# Qwiic_UV_Sensor_VEML6075.net
KiCad netlist of a schematic drawn in EAGLE
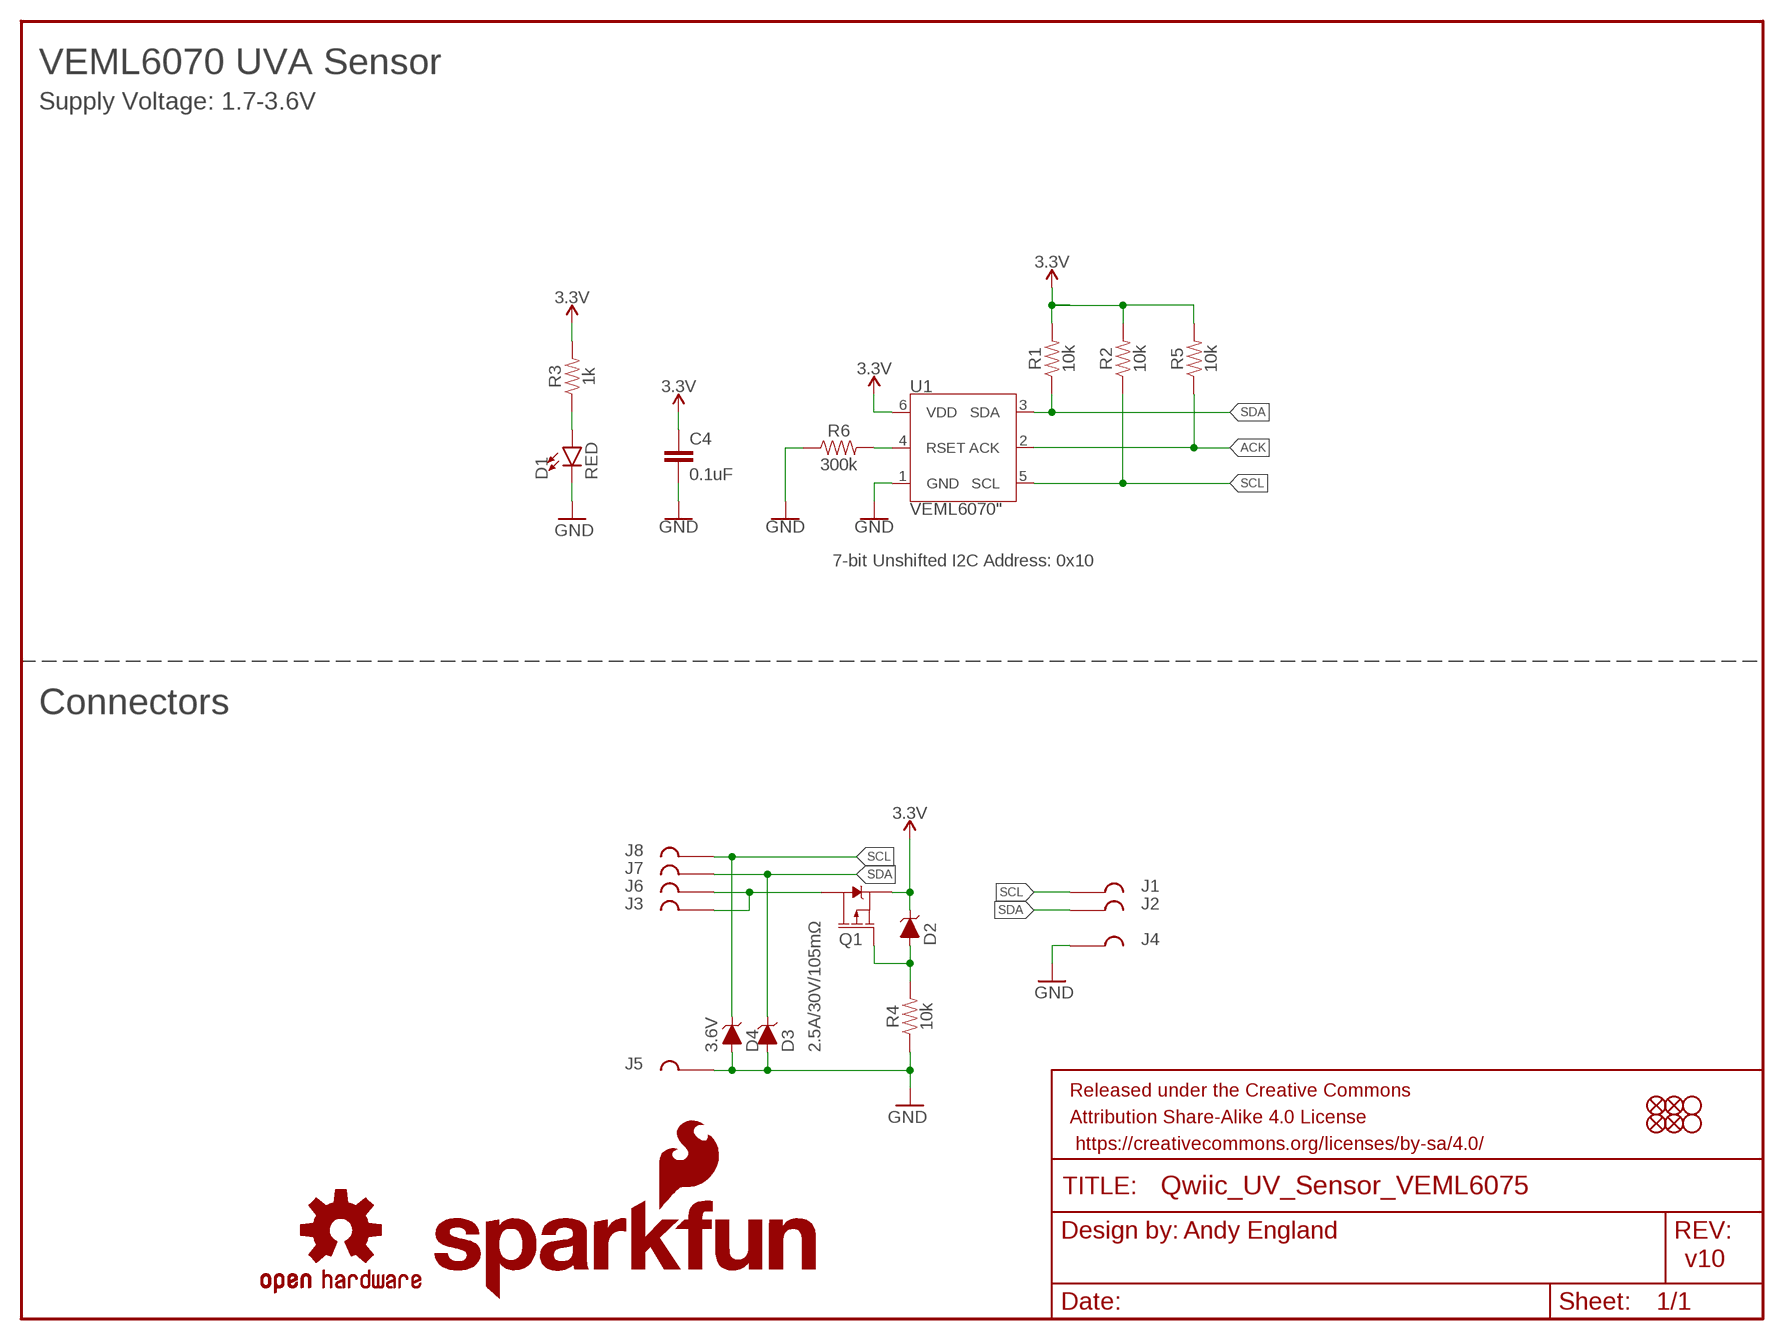
[diagram p0: schematic, sheet 1]

(export (version "E")
  (design (tool "Eeschema 10.0.6"))
  (components
    (comp (ref "C4")
      (value "0.1uF")
      (footprint "eagle-import:0603")
      (libsource (lib "eagle-import") (part "0.1UF-0603-25V-(+80/-20%)"))
    )
    (comp (ref "D1")
      (value "RED")
      (footprint "eagle-import:LED-0603")
      (libsource (lib "eagle-import") (part "LED-RED0603"))
    )
    (comp (ref "D2")
      (value "3.6V")
      (footprint "eagle-import:SOD-323")
      (libsource (lib "eagle-import") (part "DIODE-ZENER-BZT52C3V6S"))
    )
    (comp (ref "D3")
      (value "3.6V")
      (footprint "eagle-import:SOD-323")
      (libsource (lib "eagle-import") (part "DIODE-ZENER-BZT52C3V6S"))
    )
    (comp (ref "D4")
      (value "3.6V")
      (footprint "eagle-import:SOD-323")
      (libsource (lib "eagle-import") (part "DIODE-ZENER-BZT52C3V6S"))
    )
    (comp (ref "FRAME1")
      (value "FRAME-LETTER")
      (footprint "eagle-import:CREATIVE_COMMONS")
      (libsource (lib "eagle-import") (part "FRAME-LETTER"))
    )
    (comp (ref "J1")
      (value "GATORGATOR_MINI")
      (footprint "eagle-import:GATOR_MINI")
      (libsource (lib "eagle-import") (part "GATORGATOR_MINI"))
    )
    (comp (ref "J2")
      (value "GATORGATOR_MINI")
      (footprint "eagle-import:GATOR_MINI")
      (libsource (lib "eagle-import") (part "GATORGATOR_MINI"))
    )
    (comp (ref "J3")
      (value "GATORGATOR_MINI")
      (footprint "eagle-import:GATOR_MINI")
      (libsource (lib "eagle-import") (part "GATORGATOR_MINI"))
    )
    (comp (ref "J4")
      (value "GATORGATOR_MINI")
      (footprint "eagle-import:GATOR_MINI")
      (libsource (lib "eagle-import") (part "GATORGATOR_MINI"))
    )
    (comp (ref "J5")
      (value "GATORGATOR_MINI")
      (footprint "eagle-import:GATOR_MINI")
      (libsource (lib "eagle-import") (part "GATORGATOR_MINI"))
    )
    (comp (ref "J6")
      (value "GATORGATOR_MINI")
      (footprint "eagle-import:GATOR_MINI")
      (libsource (lib "eagle-import") (part "GATORGATOR_MINI"))
    )
    (comp (ref "J7")
      (value "GATORGATOR_MINI")
      (footprint "eagle-import:GATOR_MINI")
      (libsource (lib "eagle-import") (part "GATORGATOR_MINI"))
    )
    (comp (ref "J8")
      (value "GATORGATOR_MINI")
      (footprint "eagle-import:GATOR_MINI")
      (libsource (lib "eagle-import") (part "GATORGATOR_MINI"))
    )
    (comp (ref "JP2")
      (value "FIDUCIALUFIDUCIAL")
      (footprint "eagle-import:MICRO-FIDUCIAL")
      (libsource (lib "eagle-import") (part "FIDUCIALUFIDUCIAL"))
    )
    (comp (ref "JP3")
      (value "STAND-OFF")
      (footprint "eagle-import:STAND-OFF")
      (libsource (lib "eagle-import") (part "STAND-OFF"))
    )
    (comp (ref "JP4")
      (value "STAND-OFF")
      (footprint "eagle-import:STAND-OFF")
      (libsource (lib "eagle-import") (part "STAND-OFF"))
    )
    (comp (ref "JP5")
      (value "FIDUCIALUFIDUCIAL")
      (footprint "eagle-import:MICRO-FIDUCIAL")
      (libsource (lib "eagle-import") (part "FIDUCIALUFIDUCIAL"))
    )
    (comp (ref "JP6")
      (value "FIDUCIALUFIDUCIAL")
      (footprint "eagle-import:MICRO-FIDUCIAL")
      (libsource (lib "eagle-import") (part "FIDUCIALUFIDUCIAL"))
    )
    (comp (ref "JP7")
      (value "FIDUCIALUFIDUCIAL")
      (footprint "eagle-import:MICRO-FIDUCIAL")
      (libsource (lib "eagle-import") (part "FIDUCIALUFIDUCIAL"))
    )
    (comp (ref "LOGO1")
      (value "OSHW-LOGOMINI")
      (footprint "eagle-import:OSHW-LOGO-MINI")
      (libsource (lib "eagle-import") (part "OSHW-LOGOMINI"))
    )
    (comp (ref "Q1")
      (value "2.5A/30V/105mΩ")
      (footprint "eagle-import:SOT23-3")
      (libsource (lib "eagle-import") (part "MOSFET_PCH-DMG2307L"))
    )
    (comp (ref "R1")
      (value "10k")
      (footprint "eagle-import:0603")
      (libsource (lib "eagle-import") (part "10KOHM-0603-1/10W-1%"))
    )
    (comp (ref "R2")
      (value "10k")
      (footprint "eagle-import:0603")
      (libsource (lib "eagle-import") (part "10KOHM-0603-1/10W-1%"))
    )
    (comp (ref "R3")
      (value "1k")
      (footprint "eagle-import:0603")
      (libsource (lib "eagle-import") (part "1KOHM-0603-1/10W-1%"))
    )
    (comp (ref "R4")
      (value "10k")
      (footprint "eagle-import:0603")
      (libsource (lib "eagle-import") (part "10KOHM-0603-1/10W-1%"))
    )
    (comp (ref "R5")
      (value "10k")
      (footprint "eagle-import:0603")
      (libsource (lib "eagle-import") (part "10KOHM-0603-1/10W-1%"))
    )
    (comp (ref "R6")
      (value "300k")
      (footprint "eagle-import:0603")
      (libsource (lib "eagle-import") (part "300KOHM-0603-1/10W-1%"))
    )
    (comp (ref "U$1")
      (value "SFE_LOGO_NAME_FLAME.1_INCH")
      (footprint "eagle-import:SFE_LOGO_NAME_FLAME_.1")
      (libsource (lib "eagle-import") (part "SFE_LOGO_NAME_FLAME.1_INCH"))
    )
    (comp (ref "U$2")
      (value "SFE_LOGO_NAME_FLAME.1_INCH")
      (footprint "eagle-import:SFE_LOGO_NAME_FLAME_.1")
      (libsource (lib "eagle-import") (part "SFE_LOGO_NAME_FLAME.1_INCH"))
    )
    (comp (ref "U1")
      (value "VEML6070\"")
      (footprint "eagle-import:VEML6070")
      (libsource (lib "eagle-import") (part "VEML6070{dblquote}"))
    )
  )
  (nets
    (net (code "1") (name "3.3V") (class "Default")
      (node (ref "C4") (pin "1") (pinfunction "1_1") (pintype "passive"))
      (node (ref "D2") (pin "C") (pinfunction "C_C") (pintype "passive"))
      (node (ref "Q1") (pin "2") (pinfunction "S_2") (pintype "bidirectional"))
      (node (ref "R1") (pin "2") (pinfunction "2_2") (pintype "passive"))
      (node (ref "R2") (pin "2") (pinfunction "2_2") (pintype "passive"))
      (node (ref "R3") (pin "2") (pinfunction "2_2") (pintype "passive"))
      (node (ref "R5") (pin "2") (pinfunction "2_2") (pintype "passive"))
      (node (ref "U1") (pin "6") (pinfunction "VDD_6") (pintype "bidirectional"))
    )
    (net (code "2") (name "ACK") (class "Default")
      (node (ref "R5") (pin "1") (pinfunction "1_1") (pintype "passive"))
      (node (ref "U1") (pin "2") (pinfunction "ACK_2") (pintype "bidirectional"))
    )
    (net (code "3") (name "GND") (class "Default")
      (node (ref "C4") (pin "2") (pinfunction "2_2") (pintype "passive"))
      (node (ref "D1") (pin "C") (pinfunction "C_C") (pintype "passive"))
      (node (ref "D3") (pin "A") (pinfunction "A_A") (pintype "passive"))
      (node (ref "D4") (pin "A") (pinfunction "A_A") (pintype "passive"))
      (node (ref "J4") (pin "P$2") (pinfunction "P$1_P$2") (pintype "bidirectional"))
      (node (ref "J5") (pin "P$2") (pinfunction "P$1_P$2") (pintype "bidirectional"))
      (node (ref "R4") (pin "1") (pinfunction "1_1") (pintype "passive"))
      (node (ref "R6") (pin "1") (pinfunction "1_1") (pintype "passive"))
      (node (ref "U1") (pin "1") (pinfunction "GND_1") (pintype "bidirectional"))
    )
    (net (code "4") (name "Net-(D1-PadA)") (class "Default")
      (node (ref "D1") (pin "A") (pinfunction "A_A") (pintype "passive"))
      (node (ref "R3") (pin "1") (pinfunction "1_1") (pintype "passive"))
    )
    (net (code "5") (name "Net-(J3-P$1)") (class "Default")
      (node (ref "J3") (pin "P$2") (pinfunction "P$1_P$2") (pintype "bidirectional"))
      (node (ref "J6") (pin "P$2") (pinfunction "P$1_P$2") (pintype "bidirectional"))
      (node (ref "Q1") (pin "3") (pinfunction "D_3") (pintype "bidirectional"))
    )
    (net (code "6") (name "Net-(Q1-G)") (class "Default")
      (node (ref "D2") (pin "A") (pinfunction "A_A") (pintype "passive"))
      (node (ref "Q1") (pin "1") (pinfunction "G_1") (pintype "bidirectional"))
      (node (ref "R4") (pin "2") (pinfunction "2_2") (pintype "passive"))
    )
    (net (code "7") (name "Net-(U1-RSET)") (class "Default")
      (node (ref "R6") (pin "2") (pinfunction "2_2") (pintype "passive"))
      (node (ref "U1") (pin "4") (pinfunction "RSET_4") (pintype "bidirectional"))
    )
    (net (code "8") (name "SCL") (class "Default")
      (node (ref "D4") (pin "C") (pinfunction "C_C") (pintype "passive"))
      (node (ref "J1") (pin "P$2") (pinfunction "P$1_P$2") (pintype "bidirectional"))
      (node (ref "J8") (pin "P$2") (pinfunction "P$1_P$2") (pintype "bidirectional"))
      (node (ref "R2") (pin "1") (pinfunction "1_1") (pintype "passive"))
      (node (ref "U1") (pin "5") (pinfunction "SCL_5") (pintype "bidirectional"))
    )
    (net (code "9") (name "SDA") (class "Default")
      (node (ref "D3") (pin "C") (pinfunction "C_C") (pintype "passive"))
      (node (ref "J2") (pin "P$2") (pinfunction "P$1_P$2") (pintype "bidirectional"))
      (node (ref "J7") (pin "P$2") (pinfunction "P$1_P$2") (pintype "bidirectional"))
      (node (ref "R1") (pin "1") (pinfunction "1_1") (pintype "passive"))
      (node (ref "U1") (pin "3") (pinfunction "SDA_3") (pintype "bidirectional"))
    )
  )
)
